# Payloadv05.net
KiCad netlist of a schematic drawn in EAGLE
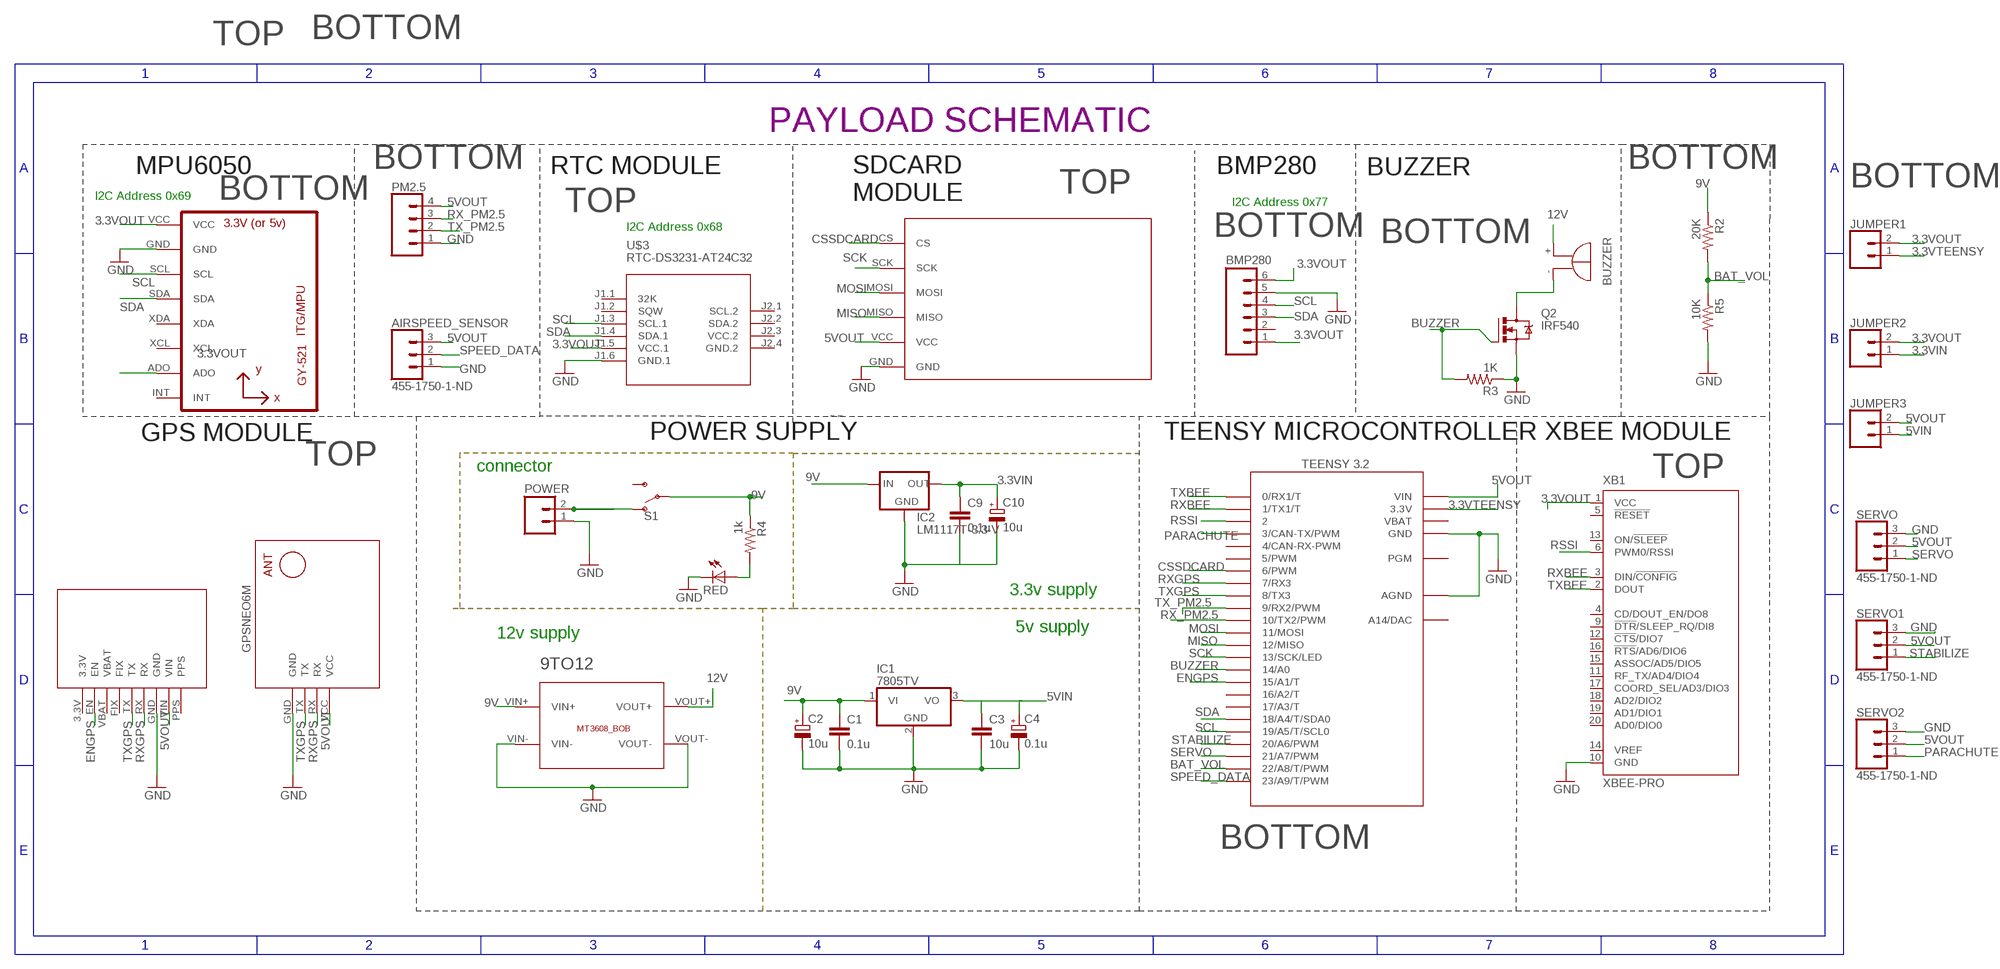
[diagram p0: schematic, sheet 1]

(export (version "E")
  (design (tool "Eeschema 10.0.6"))
  (components
    (comp (ref "9TO12")
      (value "BREAKOUTS_MT3608_BOB")
      (footprint "eagle-import:BREAKOUTS_MT3608_BOB")
      (libsource (lib "eagle-import") (part "BREAKOUTS_MT3608_BOB"))
    )
    (comp (ref "AIRSPEED_SENSOR")
      (value "455-1750-1-ND")
      (footprint "eagle-import:1X03")
      (libsource (lib "eagle-import") (part "CONN_03"))
    )
    (comp (ref "BMP280")
      (value "M06")
      (footprint "eagle-import:06P")
      (libsource (lib "eagle-import") (part "M06"))
    )
    (comp (ref "C1")
      (value "0.1u")
      (footprint "eagle-import:C025-025X050")
      (libsource (lib "eagle-import") (part "C-EU025-025X050"))
    )
    (comp (ref "C2")
      (value "10u")
      (footprint "eagle-import:E2,5-6")
      (libsource (lib "eagle-import") (part "CPOL-EUE2.5-6"))
    )
    (comp (ref "C3")
      (value "10u")
      (footprint "eagle-import:C025-025X050")
      (libsource (lib "eagle-import") (part "C-EU025-025X050"))
    )
    (comp (ref "C4")
      (value "0.1u")
      (footprint "eagle-import:E2,5-6")
      (libsource (lib "eagle-import") (part "CPOL-EUE2.5-6"))
    )
    (comp (ref "C9")
      (value "0.1u")
      (footprint "eagle-import:C025-025X050")
      (libsource (lib "eagle-import") (part "C-EU025-025X050"))
    )
    (comp (ref "C10")
      (value "10u")
      (footprint "eagle-import:E2,5-6")
      (libsource (lib "eagle-import") (part "CPOL-EUE2.5-6"))
    )
    (comp (ref "IC1")
      (value "7805TV")
      (footprint "eagle-import:TO220V")
      (libsource (lib "eagle-import") (part "78TV05"))
    )
    (comp (ref "IC2")
      (value "LM1117T-3.3-V")
      (footprint "eagle-import:TO220V")
      (libsource (lib "eagle-import") (part "LM1117T--V3.3"))
    )
    (comp (ref "JUMPER1")
      (value "CONN_02")
      (footprint "eagle-import:1X02")
      (libsource (lib "eagle-import") (part "CONN_02"))
    )
    (comp (ref "JUMPER2")
      (value "CONN_02")
      (footprint "eagle-import:1X02")
      (libsource (lib "eagle-import") (part "CONN_02"))
    )
    (comp (ref "JUMPER3")
      (value "CONN_02")
      (footprint "eagle-import:1X02")
      (libsource (lib "eagle-import") (part "CONN_02"))
    )
    (comp (ref "PM2.5")
      (value "CONN_04")
      (footprint "eagle-import:1X04")
      (libsource (lib "eagle-import") (part "CONN_04"))
    )
    (comp (ref "POWER")
      (value "CEDT_JANUARY_2015_V5_M02")
      (footprint "eagle-import:CEDT_JANUARY_2015_V5_02P")
      (libsource (lib "eagle-import") (part "CEDT_JANUARY_2015_V5_M02"))
    )
    (comp (ref "Q2")
      (value "IRF540")
      (footprint "eagle-import:TO220BV")
      (libsource (lib "eagle-import") (part "IRF540"))
    )
    (comp (ref "R2")
      (value "20K")
      (footprint "eagle-import:0204_7")
      (libsource (lib "eagle-import") (part "R-US_0204/7"))
    )
    (comp (ref "R3")
      (value "1K")
      (footprint "eagle-import:0204_7")
      (libsource (lib "eagle-import") (part "R-US_0204/7"))
    )
    (comp (ref "R4")
      (value "1k")
      (footprint "eagle-import:0204_7")
      (libsource (lib "eagle-import") (part "R-US_0204/7"))
    )
    (comp (ref "R5")
      (value "10K")
      (footprint "eagle-import:0204_7")
      (libsource (lib "eagle-import") (part "R-US_0204/7"))
    )
    (comp (ref "RED")
      (value "red")
      (footprint "eagle-import:LED3MM")
      (libsource (lib "eagle-import") (part "LED3MM"))
    )
    (comp (ref "S1")
      (value "SWITCH-SPDT-PTH-11.6X4.0MM")
      (footprint "eagle-import:SWITCH_SPDT_PTH_11.6X4.0MM")
      (libsource (lib "eagle-import") (part "SWITCH-SPDT-PTH-11.6X4.0MM"))
    )
    (comp (ref "SERVO")
      (value "455-1750-1-ND")
      (footprint "eagle-import:1X03")
      (libsource (lib "eagle-import") (part "CONN_03"))
    )
    (comp (ref "SERVO1")
      (value "455-1750-1-ND")
      (footprint "eagle-import:1X03")
      (libsource (lib "eagle-import") (part "CONN_03"))
    )
    (comp (ref "SERVO2")
      (value "455-1750-1-ND")
      (footprint "eagle-import:1X03")
      (libsource (lib "eagle-import") (part "CONN_03"))
    )
    (comp (ref "SG1")
      (value "BUZZER_EB2209A")
      (footprint "eagle-import:BUZZER_EB2209A")
      (libsource (lib "eagle-import") (part "BUZZER_EB2209A"))
    )
    (comp (ref "U$1")
      (value "GPS-RECEIVER-NEO6M")
      (footprint "eagle-import:GPS-RECEIVER-NEO6M")
      (libsource (lib "eagle-import") (part "GPS-RECEIVER-NEO6M"))
    )
    (comp (ref "U$2")
      (value "TEENSY_3.1-3.2_OUTER_ROW")
      (footprint "eagle-import:TEENSY_3.0-3.2&LC_OUTER_ROW")
      (libsource (lib "eagle-import") (part "TEENSY_3.1-3.2_OUTER_ROW"))
    )
    (comp (ref "U$3")
      (value "RTC-DS3231-AT24C32")
      (footprint "eagle-import:RTC-DS3231-AT24C32")
      (libsource (lib "eagle-import") (part "RTC-DS3231-AT24C32"))
    )
    (comp (ref "U$4")
      (value "ADAFRUIT_GPS")
      (footprint "eagle-import:ADAFRUIT_GPS")
      (libsource (lib "eagle-import") (part "ADAFRUIT_GPS"))
    )
    (comp (ref "U$5")
      (value "SDCARD")
      (footprint "eagle-import:M0SDCARDMODULE")
      (libsource (lib "eagle-import") (part "SDCARD"))
    )
    (comp (ref "U1")
      (value "GY-521MPU6050")
      (footprint "eagle-import:GY-521")
      (libsource (lib "eagle-import") (part "GY-521MPU6050"))
    )
    (comp (ref "XB1")
      (value "XBEE-PRO")
      (footprint "eagle-import:XBEE-PRO")
      (fields (field (name "MPN") "XBP24-AWI-001"))
      (libsource (lib "eagle-import") (part "XBEE-PRO"))
    )
  )
  (nets
    (net (code "1") (name "/3.3VIN") (class "Default")
      (node (ref "C10") (pin "+") (pinfunction "+_+") (pintype "passive"))
      (node (ref "C9") (pin "1") (pinfunction "1_1") (pintype "passive"))
      (node (ref "IC2") (pin "2") (pinfunction "OUT_2") (pintype "passive"))
      (node (ref "JUMPER2") (pin "1") (pinfunction "1_1") (pintype "passive"))
    )
    (net (code "2") (name "/3.3VOUT") (class "Default")
      (node (ref "BMP280") (pin "1") (pinfunction "1_1") (pintype "passive"))
      (node (ref "BMP280") (pin "6") (pinfunction "6_6") (pintype "passive"))
      (node (ref "JUMPER1") (pin "2") (pinfunction "2_2") (pintype "passive"))
      (node (ref "JUMPER2") (pin "2") (pinfunction "2_2") (pintype "passive"))
      (node (ref "U$3") (pin "J1.5") (pinfunction "VCC.1_J1.5") (pintype "power_in"))
      (node (ref "U1") (pin "ADO") (pinfunction "ADO_ADO") (pintype "bidirectional"))
      (node (ref "U1") (pin "VCC") (pinfunction "VCC_VCC") (pintype "bidirectional"))
      (node (ref "XB1") (pin "1") (pinfunction "VCC_1") (pintype "power_in"))
    )
    (net (code "3") (name "/3.3VTEENSY") (class "Default")
      (node (ref "JUMPER1") (pin "1") (pinfunction "1_1") (pintype "passive"))
      (node (ref "U$2") (pin "3.3V") (pinfunction "3.3V_3.3V") (pintype "power_in"))
      (node (ref "U$2") (pin "3.3V1") (pinfunction "3.3V_3.3V1") (pintype "power_in"))
    )
    (net (code "4") (name "/5VIN") (class "Default")
      (node (ref "C3") (pin "1") (pinfunction "1_1") (pintype "passive"))
      (node (ref "C4") (pin "+") (pinfunction "+_+") (pintype "passive"))
      (node (ref "IC1") (pin "3") (pinfunction "VO_3") (pintype "passive"))
      (node (ref "JUMPER3") (pin "1") (pinfunction "1_1") (pintype "passive"))
    )
    (net (code "5") (name "/5VOUT") (class "Default")
      (node (ref "AIRSPEED_SENSOR") (pin "3") (pinfunction "3_3") (pintype "passive"))
      (node (ref "JUMPER3") (pin "2") (pinfunction "2_2") (pintype "passive"))
      (node (ref "PM2.5") (pin "4") (pinfunction "4_4") (pintype "passive"))
      (node (ref "SERVO") (pin "2") (pinfunction "2_2") (pintype "passive"))
      (node (ref "SERVO1") (pin "2") (pinfunction "2_2") (pintype "passive"))
      (node (ref "SERVO2") (pin "2") (pinfunction "2_2") (pintype "passive"))
      (node (ref "U$1") (pin "VCC") (pinfunction "VCC_VCC") (pintype "power_in"))
      (node (ref "U$2") (pin "VIN") (pinfunction "VIN_VIN") (pintype "power_in"))
      (node (ref "U$4") (pin "VIN") (pinfunction "VIN_VIN") (pintype "bidirectional"))
      (node (ref "U$5") (pin "VCC") (pinfunction "VCC_VCC") (pintype "bidirectional"))
    )
    (net (code "6") (name "/9V") (class "Default")
      (node (ref "9TO12") (pin "VIN+") (pinfunction "VIN+_VIN+") (pintype "bidirectional"))
      (node (ref "C1") (pin "1") (pinfunction "1_1") (pintype "passive"))
      (node (ref "C2") (pin "+") (pinfunction "+_+") (pintype "passive"))
      (node (ref "IC1") (pin "1") (pinfunction "VI_1") (pintype "input"))
      (node (ref "IC2") (pin "3") (pinfunction "IN_3") (pintype "input"))
      (node (ref "R2") (pin "1") (pinfunction "1_1") (pintype "passive"))
      (node (ref "R4") (pin "1") (pinfunction "1_1") (pintype "passive"))
      (node (ref "S1") (pin "2") (pinfunction "P_2") (pintype "passive"))
    )
    (net (code "7") (name "/12V") (class "Default")
      (node (ref "9TO12") (pin "VOUT+") (pinfunction "VOUT+_VOUT+") (pintype "bidirectional"))
      (node (ref "SG1") (pin "+") (pinfunction "+_+") (pintype "passive"))
    )
    (net (code "8") (name "/BAT_VOL") (class "Default")
      (node (ref "R2") (pin "2") (pinfunction "2_2") (pintype "passive"))
      (node (ref "R5") (pin "1") (pinfunction "1_1") (pintype "passive"))
      (node (ref "U$2") (pin "22/A8") (pinfunction "22/A8/T/PWM_22/A8") (pintype "bidirectional"))
    )
    (net (code "9") (name "/BUZZER") (class "Default")
      (node (ref "Q2") (pin "G") (pinfunction "G_G") (pintype "passive"))
      (node (ref "R3") (pin "2") (pinfunction "2_2") (pintype "passive"))
      (node (ref "U$2") (pin "14/A0") (pinfunction "14/A0_14/A0") (pintype "bidirectional"))
    )
    (net (code "10") (name "/CSSDCARD") (class "Default")
      (node (ref "U$2") (pin "6") (pinfunction "6/PWM_6") (pintype "bidirectional"))
      (node (ref "U$5") (pin "CS") (pinfunction "CS_CS") (pintype "bidirectional"))
    )
    (net (code "11") (name "/ENGPS") (class "Default")
      (node (ref "U$2") (pin "15/A1") (pinfunction "15/A1/T_15/A1") (pintype "bidirectional"))
      (node (ref "U$4") (pin "EN") (pinfunction "EN_EN") (pintype "bidirectional"))
    )
    (net (code "12") (name "/GND.2") (class "Default")
      (node (ref "U$3") (pin "J2.4") (pinfunction "GND.2_J2.4") (pintype "power_in"))
    )
    (net (code "13") (name "/MISO") (class "Default")
      (node (ref "U$2") (pin "12") (pinfunction "12/MISO_12") (pintype "bidirectional"))
      (node (ref "U$5") (pin "MISO") (pinfunction "MISO_MISO") (pintype "bidirectional"))
    )
    (net (code "14") (name "/MOSI") (class "Default")
      (node (ref "U$2") (pin "11") (pinfunction "11/MOSI_11") (pintype "bidirectional"))
      (node (ref "U$5") (pin "MOSI") (pinfunction "MOSI_MOSI") (pintype "bidirectional"))
    )
    (net (code "15") (name "/PARACHUTE") (class "Default")
      (node (ref "SERVO2") (pin "1") (pinfunction "1_1") (pintype "passive"))
      (node (ref "U$2") (pin "3") (pinfunction "3/CAN-TX/PWM_3") (pintype "bidirectional"))
    )
    (net (code "16") (name "/RSSI") (class "Default")
      (node (ref "U$2") (pin "2") (pinfunction "2_2") (pintype "bidirectional"))
      (node (ref "XB1") (pin "6") (pinfunction "PWM0/RSSI_6") (pintype "output"))
    )
    (net (code "17") (name "/RXBEE") (class "Default")
      (node (ref "U$2") (pin "1") (pinfunction "1/TX1/T_1") (pintype "bidirectional"))
      (node (ref "XB1") (pin "3") (pinfunction "DIN/~{CONFIG}_3") (pintype "input"))
    )
    (net (code "18") (name "/RXGPS") (class "Default")
      (node (ref "U$1") (pin "RX") (pinfunction "RX_RX") (pintype "bidirectional"))
      (node (ref "U$2") (pin "7") (pinfunction "7/RX3_7") (pintype "bidirectional"))
      (node (ref "U$4") (pin "RX") (pinfunction "RX_RX") (pintype "bidirectional"))
    )
    (net (code "19") (name "/RX_PM2.5") (class "Default")
      (node (ref "PM2.5") (pin "3") (pinfunction "3_3") (pintype "passive"))
      (node (ref "U$2") (pin "10") (pinfunction "10/TX2/PWM_10") (pintype "bidirectional"))
    )
    (net (code "20") (name "/SCK") (class "Default")
      (node (ref "U$2") (pin "13") (pinfunction "13/SCK/LED_13") (pintype "bidirectional"))
      (node (ref "U$5") (pin "SCK") (pinfunction "SCK_SCK") (pintype "bidirectional"))
    )
    (net (code "21") (name "/SCL") (class "Default")
      (node (ref "BMP280") (pin "4") (pinfunction "4_4") (pintype "passive"))
      (node (ref "U$2") (pin "19/A5") (pinfunction "19/A5/T/SCL0_19/A5") (pintype "bidirectional"))
      (node (ref "U$3") (pin "J1.3") (pinfunction "SCL.1_J1.3") (pintype "bidirectional"))
      (node (ref "U1") (pin "SCL") (pinfunction "SCL_SCL") (pintype "bidirectional"))
    )
    (net (code "22") (name "/SDA") (class "Default")
      (node (ref "BMP280") (pin "3") (pinfunction "3_3") (pintype "passive"))
      (node (ref "U$2") (pin "18/A4") (pinfunction "18/A4/T/SDA0_18/A4") (pintype "bidirectional"))
      (node (ref "U$3") (pin "J1.4") (pinfunction "SDA.1_J1.4") (pintype "bidirectional"))
      (node (ref "U1") (pin "SDA") (pinfunction "SDA_SDA") (pintype "bidirectional"))
    )
    (net (code "23") (name "/SERVO") (class "Default")
      (node (ref "SERVO") (pin "1") (pinfunction "1_1") (pintype "passive"))
      (node (ref "U$2") (pin "21/A7") (pinfunction "21/A7/PWM_21/A7") (pintype "bidirectional"))
    )
    (net (code "24") (name "/SPEED_DATA") (class "Default")
      (node (ref "AIRSPEED_SENSOR") (pin "2") (pinfunction "2_2") (pintype "passive"))
      (node (ref "U$2") (pin "23/A9") (pinfunction "23/A9/T/PWM_23/A9") (pintype "bidirectional"))
    )
    (net (code "25") (name "/STABILIZE") (class "Default")
      (node (ref "SERVO1") (pin "1") (pinfunction "1_1") (pintype "passive"))
      (node (ref "U$2") (pin "20/A6") (pinfunction "20/A6/PWM_20/A6") (pintype "bidirectional"))
    )
    (net (code "26") (name "/TXBEE") (class "Default")
      (node (ref "U$2") (pin "0") (pinfunction "0/RX1/T_0") (pintype "bidirectional"))
      (node (ref "XB1") (pin "2") (pinfunction "DOUT_2") (pintype "output"))
    )
    (net (code "27") (name "/TXGPS") (class "Default")
      (node (ref "U$1") (pin "TX") (pinfunction "TX_TX") (pintype "bidirectional"))
      (node (ref "U$2") (pin "8") (pinfunction "8/TX3_8") (pintype "bidirectional"))
      (node (ref "U$4") (pin "TX") (pinfunction "TX_TX") (pintype "bidirectional"))
    )
    (net (code "28") (name "/TX_PM2.5") (class "Default")
      (node (ref "PM2.5") (pin "2") (pinfunction "2_2") (pintype "passive"))
      (node (ref "U$2") (pin "9") (pinfunction "9/RX2/PWM_9") (pintype "bidirectional"))
    )
    (net (code "29") (name "/VBAT") (class "Default")
      (node (ref "U$2") (pin "VBAT") (pinfunction "VBAT_VBAT") (pintype "power_in"))
    )
    (net (code "30") (name "/VCC.2") (class "Default")
      (node (ref "U$3") (pin "J2.3") (pinfunction "VCC.2_J2.3") (pintype "power_in"))
    )
    (net (code "31") (name "GND") (class "Default")
      (node (ref "9TO12") (pin "VIN-") (pinfunction "VIN-_VIN-") (pintype "bidirectional"))
      (node (ref "9TO12") (pin "VOUT-") (pinfunction "VOUT-_VOUT-") (pintype "bidirectional"))
      (node (ref "AIRSPEED_SENSOR") (pin "1") (pinfunction "1_1") (pintype "passive"))
      (node (ref "BMP280") (pin "5") (pinfunction "5_5") (pintype "passive"))
      (node (ref "C1") (pin "2") (pinfunction "2_2") (pintype "passive"))
      (node (ref "C10") (pin "-") (pinfunction "-_-") (pintype "passive"))
      (node (ref "C2") (pin "-") (pinfunction "-_-") (pintype "passive"))
      (node (ref "C3") (pin "2") (pinfunction "2_2") (pintype "passive"))
      (node (ref "C4") (pin "-") (pinfunction "-_-") (pintype "passive"))
      (node (ref "C9") (pin "2") (pinfunction "2_2") (pintype "passive"))
      (node (ref "IC1") (pin "2") (pinfunction "GND_2") (pintype "passive"))
      (node (ref "IC2") (pin "1") (pinfunction "GND_1") (pintype "input"))
      (node (ref "PM2.5") (pin "1") (pinfunction "1_1") (pintype "passive"))
      (node (ref "POWER") (pin "1") (pinfunction "1_1") (pintype "passive"))
      (node (ref "Q2") (pin "S") (pinfunction "S_S") (pintype "passive"))
      (node (ref "R3") (pin "1") (pinfunction "1_1") (pintype "passive"))
      (node (ref "R5") (pin "2") (pinfunction "2_2") (pintype "passive"))
      (node (ref "RED") (pin "K") (pinfunction "C_K") (pintype "passive"))
      (node (ref "SERVO") (pin "3") (pinfunction "3_3") (pintype "passive"))
      (node (ref "SERVO1") (pin "3") (pinfunction "3_3") (pintype "passive"))
      (node (ref "SERVO2") (pin "3") (pinfunction "3_3") (pintype "passive"))
      (node (ref "U$1") (pin "GND") (pinfunction "GND_GND") (pintype "bidirectional"))
      (node (ref "U$2") (pin "AGND") (pinfunction "AGND_AGND") (pintype "power_in"))
      (node (ref "U$2") (pin "GND") (pinfunction "GND_GND") (pintype "power_in"))
      (node (ref "U$2") (pin "GND1") (pinfunction "GND_GND1") (pintype "power_in"))
      (node (ref "U$3") (pin "J1.6") (pinfunction "GND.1_J1.6") (pintype "power_in"))
      (node (ref "U$4") (pin "GND") (pinfunction "GND_GND") (pintype "bidirectional"))
      (node (ref "U$5") (pin "GND") (pinfunction "GND_GND") (pintype "bidirectional"))
      (node (ref "U1") (pin "GND") (pinfunction "GND_GND") (pintype "bidirectional"))
      (node (ref "XB1") (pin "10") (pinfunction "GND_10") (pintype "power_in"))
    )
    (net (code "32") (name "Net-(Q2-PadD)") (class "Default")
      (node (ref "Q2") (pin "D") (pinfunction "D_D") (pintype "passive"))
      (node (ref "SG1") (pin "-") (pinfunction "-_-") (pintype "passive"))
    )
    (net (code "33") (name "Net-(R4-Pad2)") (class "Default")
      (node (ref "R4") (pin "2") (pinfunction "2_2") (pintype "passive"))
      (node (ref "RED") (pin "A") (pinfunction "A_A") (pintype "passive"))
    )
    (net (code "34") (name "Net-(S1-O)") (class "Default")
      (node (ref "POWER") (pin "2") (pinfunction "2_2") (pintype "passive"))
      (node (ref "S1") (pin "1") (pinfunction "O_1") (pintype "passive"))
    )
    (net (code "35") (name "unconnected-(BMP280-Pad2)") (class "Default")
      (node (ref "BMP280") (pin "2") (pinfunction "2_2") (pintype "passive"))
    )
    (net (code "36") (name "unconnected-(S1-S-Pad3)") (class "Default")
      (node (ref "S1") (pin "3") (pinfunction "S_3") (pintype "passive"))
    )
    (net (code "37") (name "unconnected-(U$2-4{slash}CAN-RX-PWM-Pad4)") (class "Default")
      (node (ref "U$2") (pin "4") (pinfunction "4/CAN-RX-PWM_4") (pintype "bidirectional"))
    )
    (net (code "38") (name "unconnected-(U$2-5{slash}PWM-Pad5)") (class "Default")
      (node (ref "U$2") (pin "5") (pinfunction "5/PWM_5") (pintype "bidirectional"))
    )
    (net (code "39") (name "unconnected-(U$2-16{slash}A2{slash}T-Pad16{slash}A2)") (class "Default")
      (node (ref "U$2") (pin "16/A2") (pinfunction "16/A2/T_16/A2") (pintype "bidirectional"))
    )
    (net (code "40") (name "unconnected-(U$2-17{slash}A3{slash}T-Pad17{slash}A3)") (class "Default")
      (node (ref "U$2") (pin "17/A3") (pinfunction "17/A3/T_17/A3") (pintype "bidirectional"))
    )
    (net (code "41") (name "unconnected-(U$2-A14{slash}DAC-PadRESET{slash}DAC)") (class "Default")
      (node (ref "U$2") (pin "RESET/DAC") (pinfunction "A14/DAC_RESET/DAC") (pintype "bidirectional"))
    )
    (net (code "42") (name "unconnected-(U$2-PadPGM)") (class "Default")
      (node (ref "U$2") (pin "PGM") (pinfunction "PGM_PGM") (pintype "bidirectional"))
    )
    (net (code "43") (name "unconnected-(U$3-32K-PadJ1.1)") (class "Default")
      (node (ref "U$3") (pin "J1.1") (pinfunction "32K_J1.1") (pintype "bidirectional"))
    )
    (net (code "44") (name "unconnected-(U$3-SCL.2-PadJ2.1)") (class "Default")
      (node (ref "U$3") (pin "J2.1") (pinfunction "SCL.2_J2.1") (pintype "bidirectional"))
    )
    (net (code "45") (name "unconnected-(U$3-SDA.2-PadJ2.2)") (class "Default")
      (node (ref "U$3") (pin "J2.2") (pinfunction "SDA.2_J2.2") (pintype "bidirectional"))
    )
    (net (code "46") (name "unconnected-(U$3-SQW-PadJ1.2)") (class "Default")
      (node (ref "U$3") (pin "J1.2") (pinfunction "SQW_J1.2") (pintype "bidirectional"))
    )
    (net (code "47") (name "unconnected-(U$4-Pad3.3V)") (class "Default")
      (node (ref "U$4") (pin "3.3V") (pinfunction "3.3V_3.3V") (pintype "bidirectional"))
    )
    (net (code "48") (name "unconnected-(U$4-PadFIX)") (class "Default")
      (node (ref "U$4") (pin "FIX") (pinfunction "FIX_FIX") (pintype "bidirectional"))
    )
    (net (code "49") (name "unconnected-(U$4-PadPPS)") (class "Default")
      (node (ref "U$4") (pin "PPS") (pinfunction "PPS_PPS") (pintype "bidirectional"))
    )
    (net (code "50") (name "unconnected-(U$4-PadVBAT)") (class "Default")
      (node (ref "U$4") (pin "VBAT") (pinfunction "VBAT_VBAT") (pintype "bidirectional"))
    )
    (net (code "51") (name "unconnected-(U1-PadINT)") (class "Default")
      (node (ref "U1") (pin "INT") (pinfunction "INT_INT") (pintype "bidirectional"))
    )
    (net (code "52") (name "unconnected-(U1-PadXCL)") (class "Default")
      (node (ref "U1") (pin "XCL") (pinfunction "XCL_XCL") (pintype "bidirectional"))
    )
    (net (code "53") (name "unconnected-(U1-PadXDA)") (class "Default")
      (node (ref "U1") (pin "XDA") (pinfunction "XDA_XDA") (pintype "bidirectional"))
    )
    (net (code "54") (name "unconnected-(XB1-AD0{slash}DIO0-Pad20)") (class "Default")
      (node (ref "XB1") (pin "20") (pinfunction "AD0/DIO0_20") (pintype "bidirectional"))
    )
    (net (code "55") (name "unconnected-(XB1-AD1{slash}DIO1-Pad19)") (class "Default")
      (node (ref "XB1") (pin "19") (pinfunction "AD1/DIO1_19") (pintype "bidirectional"))
    )
    (net (code "56") (name "unconnected-(XB1-AD2{slash}DIO2-Pad18)") (class "Default")
      (node (ref "XB1") (pin "18") (pinfunction "AD2/DIO2_18") (pintype "bidirectional"))
    )
    (net (code "57") (name "unconnected-(XB1-ASSOC{slash}AD5{slash}DIO5-Pad15)") (class "Default")
      (node (ref "XB1") (pin "15") (pinfunction "ASSOC/AD5/DIO5_15") (pintype "bidirectional"))
    )
    (net (code "58") (name "unconnected-(XB1-CD{slash}DOUT_EN{slash}DO8-Pad4)") (class "Default")
      (node (ref "XB1") (pin "4") (pinfunction "CD/DOUT_EN/DO8_4") (pintype "output"))
    )
    (net (code "59") (name "unconnected-(XB1-COORD_SEL{slash}AD3{slash}DIO3-Pad17)") (class "Default")
      (node (ref "XB1") (pin "17") (pinfunction "COORD_SEL/AD3/DIO3_17") (pintype "bidirectional"))
    )
    (net (code "60") (name "unconnected-(XB1-ON{slash}~{SLEEP}-Pad13)") (class "Default")
      (node (ref "XB1") (pin "13") (pinfunction "ON/~{SLEEP}_13") (pintype "output"))
    )
    (net (code "61") (name "unconnected-(XB1-RF_TX{slash}AD4{slash}DIO4-Pad11)") (class "Default")
      (node (ref "XB1") (pin "11") (pinfunction "RF_TX/AD4/DIO4_11") (pintype "bidirectional"))
    )
    (net (code "62") (name "unconnected-(XB1-VREF-Pad14)") (class "Default")
      (node (ref "XB1") (pin "14") (pinfunction "VREF_14") (pintype "input"))
    )
    (net (code "63") (name "unconnected-(XB1-~{CTS}{slash}DIO7-Pad12)") (class "Default")
      (node (ref "XB1") (pin "12") (pinfunction "~{CTS}/DIO7_12") (pintype "bidirectional"))
    )
    (net (code "64") (name "unconnected-(XB1-~{DTR}{slash}SLEEP_RQ{slash}DI8-Pad9)") (class "Default")
      (node (ref "XB1") (pin "9") (pinfunction "~{DTR}/SLEEP_RQ/DI8_9") (pintype "bidirectional"))
    )
    (net (code "65") (name "unconnected-(XB1-~{RESET}-Pad5)") (class "Default")
      (node (ref "XB1") (pin "5") (pinfunction "~{RESET}_5") (pintype "input"))
    )
    (net (code "66") (name "unconnected-(XB1-~{RTS}{slash}AD6{slash}DIO6-Pad16)") (class "Default")
      (node (ref "XB1") (pin "16") (pinfunction "~{RTS}/AD6/DIO6_16") (pintype "bidirectional"))
    )
  )
)
